# CDH-v3_7.net
KiCad netlist of a schematic drawn in EAGLE
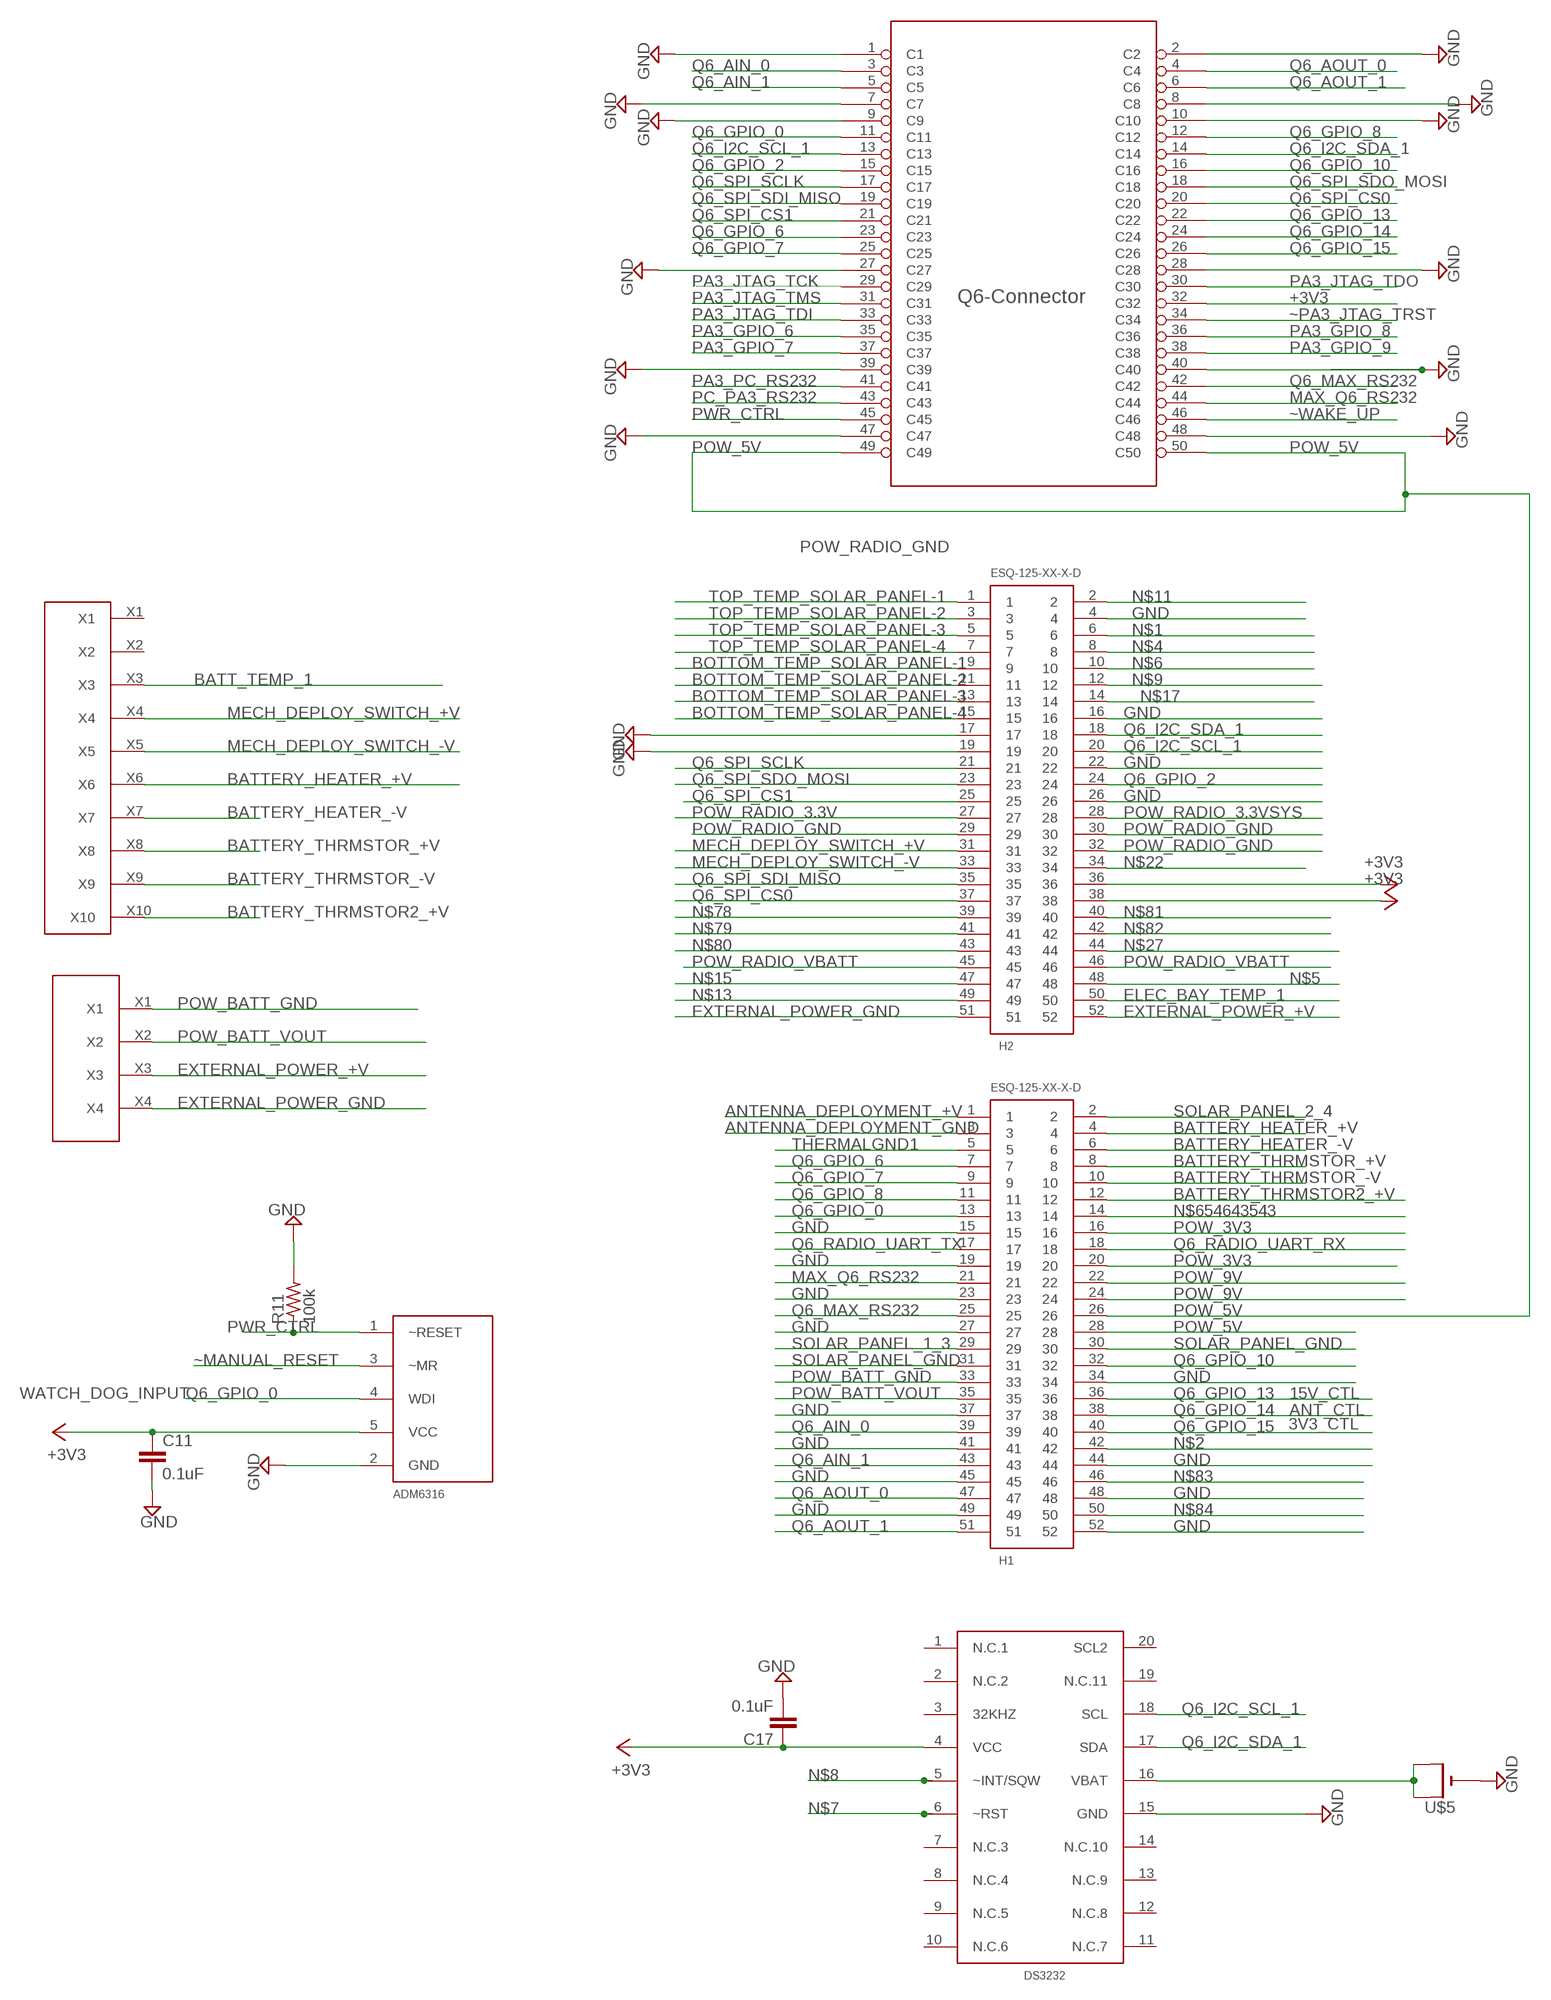
[diagram p0: schematic, sheet 1, part 1 of 2]
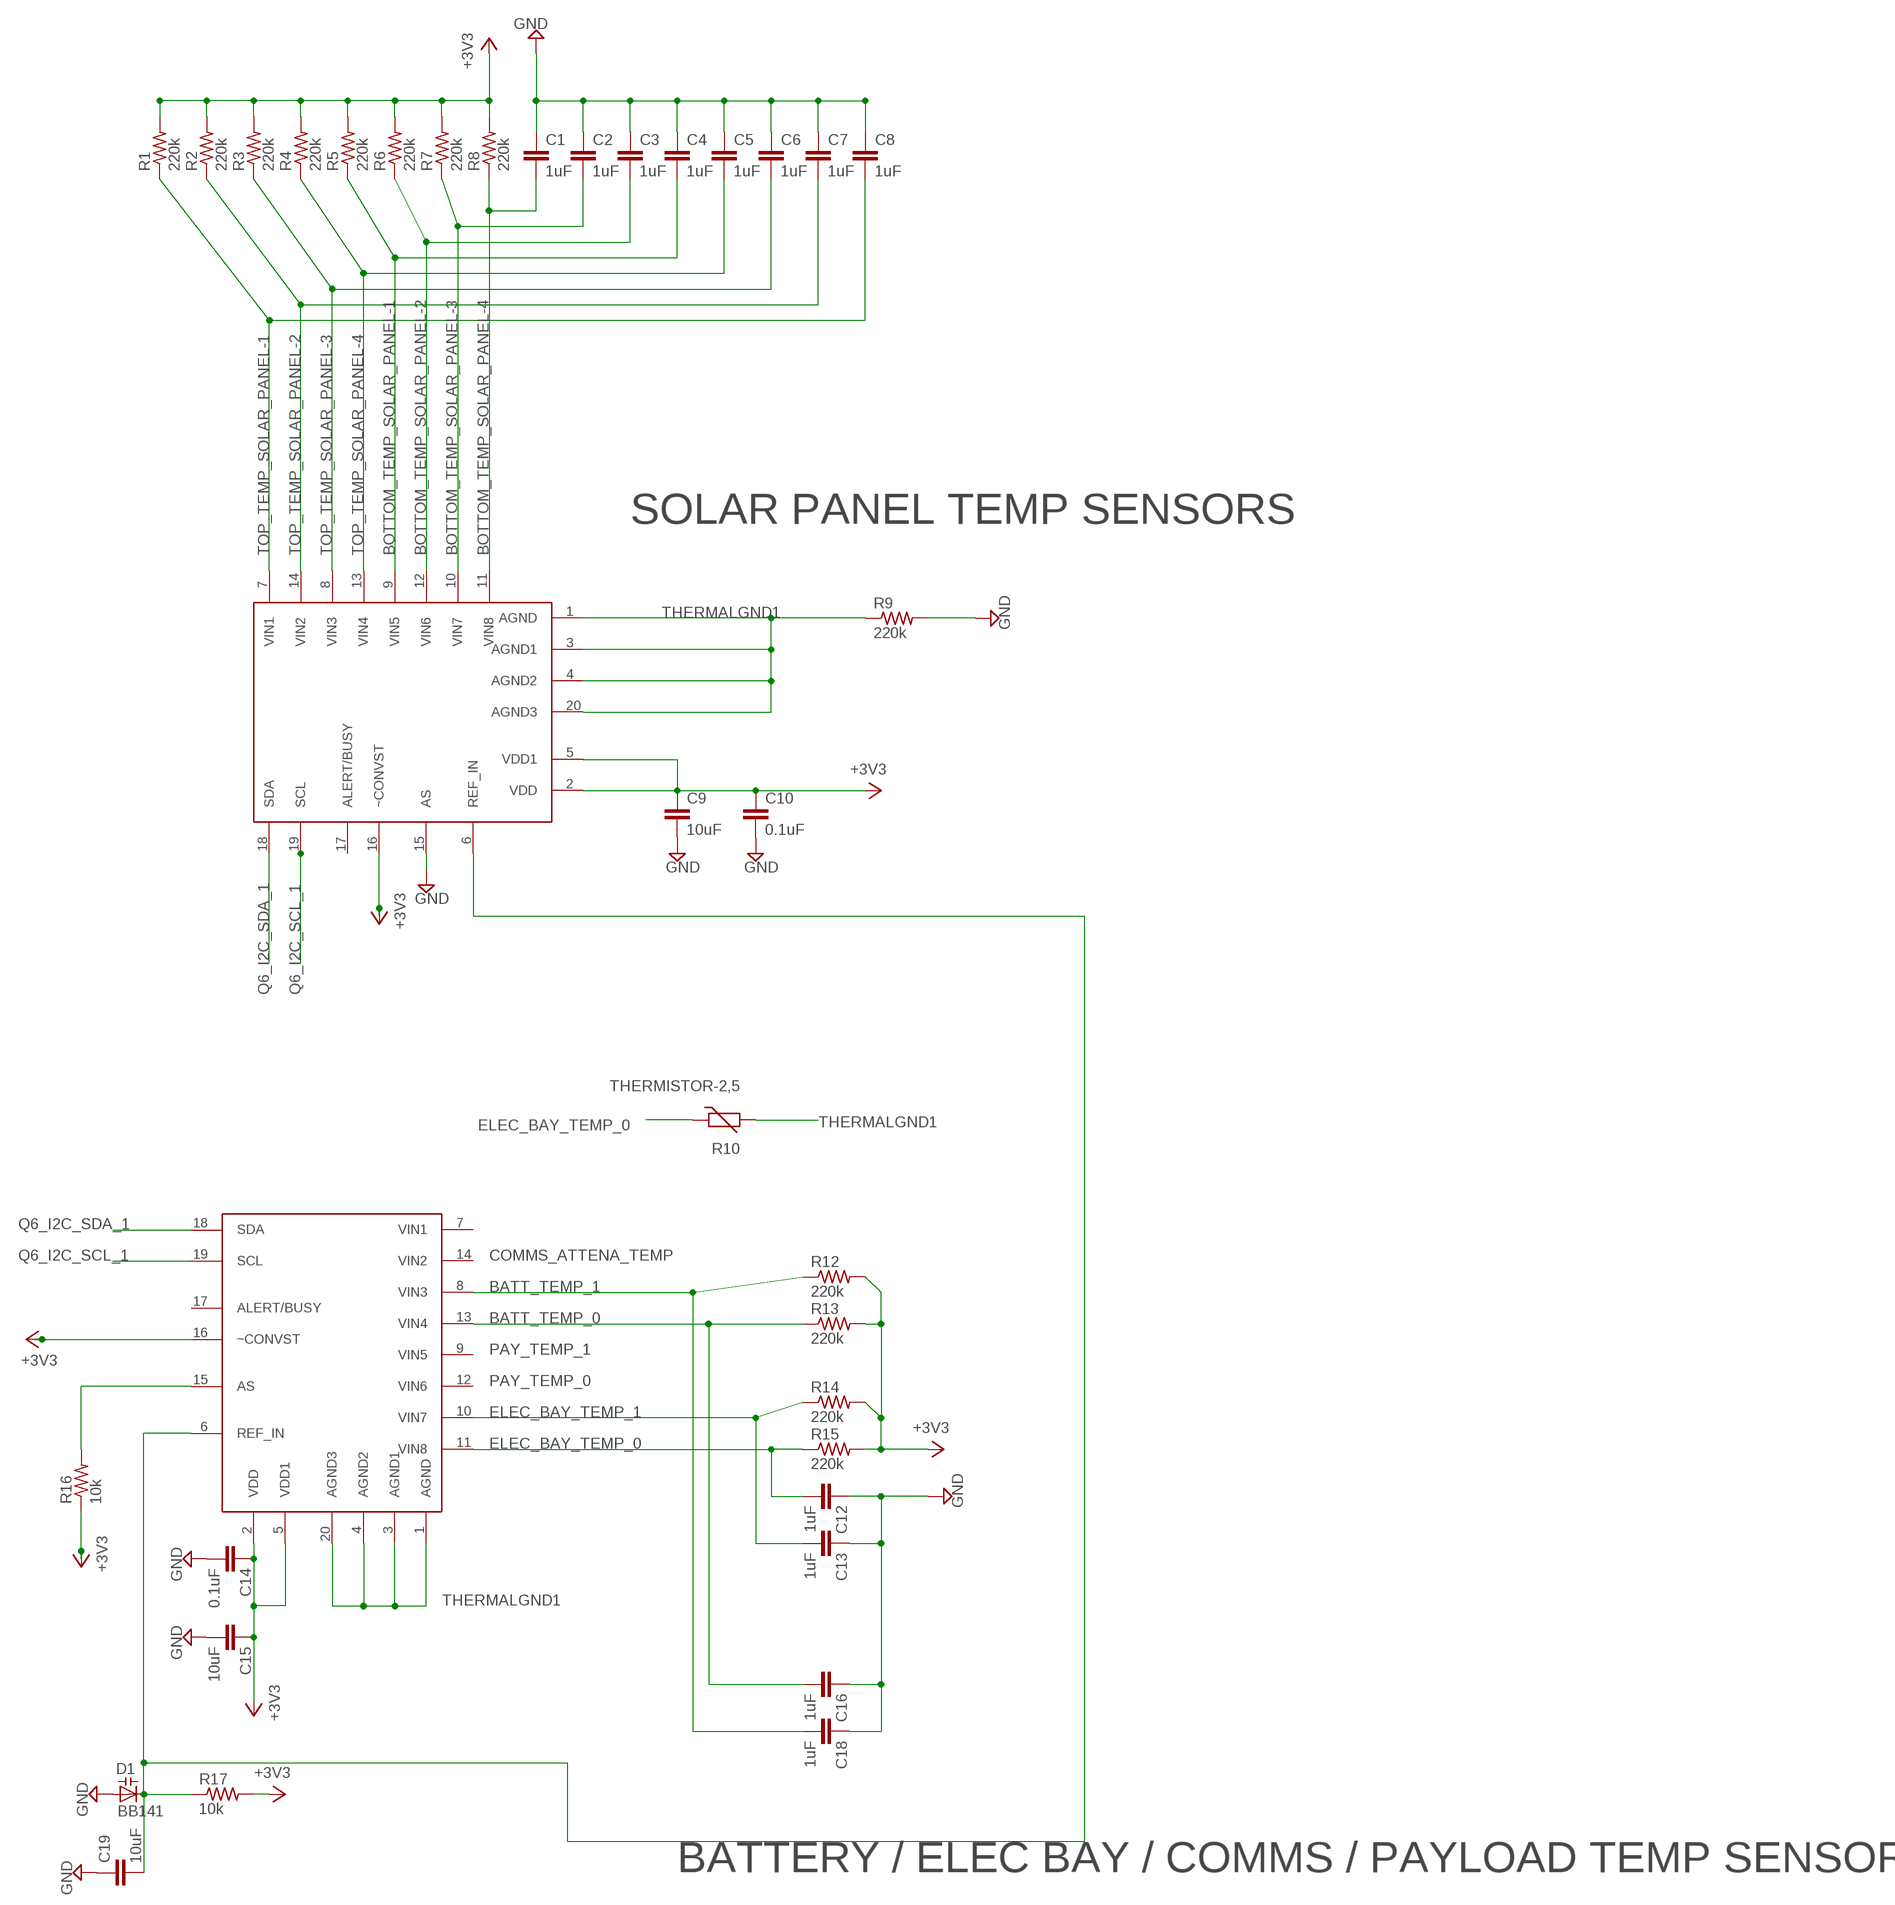
[diagram p1: schematic, sheet 1, part 2 of 2]

(export (version "E")
  (design (tool "Eeschema 10.0.6"))
  (components
    (comp (ref "ADC_TEMP_1")
      (value "AD7998-1")
      (footprint "eagle-import:TSSOP20")
      (libsource (lib "eagle-import") (part "AD7998-1"))
    )
    (comp (ref "ADC_TEMP_2")
      (value "AD7998-1")
      (footprint "eagle-import:TSSOP20")
      (libsource (lib "eagle-import") (part "AD7998-1"))
    )
    (comp (ref "C1")
      (value "1uF")
      (footprint "eagle-import:C2012")
      (libsource (lib "eagle-import") (part "C-EUC2012"))
    )
    (comp (ref "C2")
      (value "1uF")
      (footprint "eagle-import:C2012")
      (libsource (lib "eagle-import") (part "C-EUC2012"))
    )
    (comp (ref "C3")
      (value "1uF")
      (footprint "eagle-import:C2012")
      (libsource (lib "eagle-import") (part "C-EUC2012"))
    )
    (comp (ref "C4")
      (value "1uF")
      (footprint "eagle-import:C2012")
      (libsource (lib "eagle-import") (part "C-EUC2012"))
    )
    (comp (ref "C5")
      (value "1uF")
      (footprint "eagle-import:C2012")
      (libsource (lib "eagle-import") (part "C-EUC2012"))
    )
    (comp (ref "C6")
      (value "1uF")
      (footprint "eagle-import:C2012")
      (libsource (lib "eagle-import") (part "C-EUC2012"))
    )
    (comp (ref "C7")
      (value "1uF")
      (footprint "eagle-import:C2012")
      (libsource (lib "eagle-import") (part "C-EUC2012"))
    )
    (comp (ref "C8")
      (value "1uF")
      (footprint "eagle-import:C2012")
      (libsource (lib "eagle-import") (part "C-EUC2012"))
    )
    (comp (ref "C9")
      (value "10uF")
      (footprint "eagle-import:C2012")
      (libsource (lib "eagle-import") (part "C-EUC2012"))
    )
    (comp (ref "C10")
      (value "0.1uF")
      (footprint "eagle-import:C2012")
      (libsource (lib "eagle-import") (part "C-EUC2012"))
    )
    (comp (ref "C11")
      (value "0.1uF")
      (footprint "eagle-import:C2012")
      (libsource (lib "eagle-import") (part "C-EUC2012"))
    )
    (comp (ref "C12")
      (value "1uF")
      (footprint "eagle-import:C2012")
      (libsource (lib "eagle-import") (part "C-EUC2012"))
    )
    (comp (ref "C13")
      (value "1uF")
      (footprint "eagle-import:C2012")
      (libsource (lib "eagle-import") (part "C-EUC2012"))
    )
    (comp (ref "C14")
      (value "0.1uF")
      (footprint "eagle-import:C2012")
      (libsource (lib "eagle-import") (part "C-EUC2012"))
    )
    (comp (ref "C15")
      (value "10uF")
      (footprint "eagle-import:C2012")
      (libsource (lib "eagle-import") (part "C-EUC2012"))
    )
    (comp (ref "C16")
      (value "1uF")
      (footprint "eagle-import:C2012")
      (libsource (lib "eagle-import") (part "C-EUC2012"))
    )
    (comp (ref "C17")
      (value "0.1uF")
      (footprint "eagle-import:C2012")
      (libsource (lib "eagle-import") (part "C-EUC2012"))
    )
    (comp (ref "C18")
      (value "1uF")
      (footprint "eagle-import:C2012")
      (libsource (lib "eagle-import") (part "C-EUC2012"))
    )
    (comp (ref "C19")
      (value "10uF")
      (footprint "eagle-import:C2012")
      (libsource (lib "eagle-import") (part "C-EUC2012"))
    )
    (comp (ref "D1")
      (value "BB141")
      (footprint "eagle-import:SOD523")
      (libsource (lib "eagle-import") (part "BB141"))
    )
    (comp (ref "H1")
      (value "ESQ-125-XX-X-D")
      (footprint "eagle-import:ESQ-125-XX-X-D")
      (libsource (lib "eagle-import") (part "ESQ-125-XX-X-D"))
    )
    (comp (ref "H2")
      (value "ESQ-125-XX-X-D")
      (footprint "eagle-import:ESQ-125-XX-X-D")
      (libsource (lib "eagle-import") (part "ESQ-125-XX-X-D"))
    )
    (comp (ref "J2")
      (value "M80-5000000M1-10-331-000")
      (footprint "eagle-import:M80-5000000M1")
      (libsource (lib "eagle-import") (part "M80-5000000M1-10-331-000"))
    )
    (comp (ref "J3")
      (value "M80-5000000M1-10-331-00-000")
      (footprint "eagle-import:M80-5000000M1-04-331-00-000")
      (libsource (lib "eagle-import") (part "M80-5000000M1-10-331-00-000"))
    )
    (comp (ref "J4")
      (value "SMFC")
      (footprint "eagle-import:SFMC-107-01-XX-D")
      (libsource (lib "eagle-import") (part "SMFC"))
    )
    (comp (ref "R1")
      (value "220k")
      (footprint "eagle-import:R2012")
      (libsource (lib "eagle-import") (part "R-US_R2012"))
    )
    (comp (ref "R2")
      (value "220k")
      (footprint "eagle-import:R2012")
      (libsource (lib "eagle-import") (part "R-US_R2012"))
    )
    (comp (ref "R3")
      (value "220k")
      (footprint "eagle-import:R2012")
      (libsource (lib "eagle-import") (part "R-US_R2012"))
    )
    (comp (ref "R4")
      (value "220k")
      (footprint "eagle-import:R2012")
      (libsource (lib "eagle-import") (part "R-US_R2012"))
    )
    (comp (ref "R5")
      (value "220k")
      (footprint "eagle-import:R2012")
      (libsource (lib "eagle-import") (part "R-US_R2012"))
    )
    (comp (ref "R6")
      (value "220k")
      (footprint "eagle-import:R2012")
      (libsource (lib "eagle-import") (part "R-US_R2012"))
    )
    (comp (ref "R7")
      (value "220k")
      (footprint "eagle-import:R2012")
      (libsource (lib "eagle-import") (part "R-US_R2012"))
    )
    (comp (ref "R8")
      (value "220k")
      (footprint "eagle-import:R2012")
      (libsource (lib "eagle-import") (part "R-US_R2012"))
    )
    (comp (ref "R9")
      (value "220k")
      (footprint "eagle-import:R2012")
      (libsource (lib "eagle-import") (part "R-US_R2012"))
    )
    (comp (ref "R10")
      (value "THERMISTOR-2,5")
      (footprint "eagle-import:RS-2,5")
      (libsource (lib "eagle-import") (part "THERMISTOR-2,5"))
    )
    (comp (ref "R11")
      (value "100k")
      (footprint "eagle-import:R2012")
      (libsource (lib "eagle-import") (part "R-US_R2012"))
    )
    (comp (ref "R12")
      (value "220k")
      (footprint "eagle-import:R2012")
      (libsource (lib "eagle-import") (part "R-US_R2012"))
    )
    (comp (ref "R13")
      (value "220k")
      (footprint "eagle-import:R2012")
      (libsource (lib "eagle-import") (part "R-US_R2012"))
    )
    (comp (ref "R14")
      (value "220k")
      (footprint "eagle-import:R2012")
      (libsource (lib "eagle-import") (part "R-US_R2012"))
    )
    (comp (ref "R15")
      (value "220k")
      (footprint "eagle-import:R2012")
      (libsource (lib "eagle-import") (part "R-US_R2012"))
    )
    (comp (ref "R16")
      (value "10k")
      (footprint "eagle-import:R2012")
      (libsource (lib "eagle-import") (part "R-US_R2012"))
    )
    (comp (ref "R17")
      (value "10k")
      (footprint "eagle-import:R2012")
      (libsource (lib "eagle-import") (part "R-US_R2012"))
    )
    (comp (ref "U$4")
      (value "ADM6316/ADM6320")
      (footprint "eagle-import:SOT23-5")
      (libsource (lib "eagle-import") (part "ADM6316/ADM6320"))
    )
    (comp (ref "U$5")
      (value "CR1220SMT")
      (footprint "eagle-import:CR1220-SMD")
      (libsource (lib "eagle-import") (part "CR1220SMT"))
    )
    (comp (ref "U$6")
      (value "DS3232")
      (footprint "eagle-import:SO20L")
      (libsource (lib "eagle-import") (part "DS3232"))
    )
  )
  (nets
    (net (code "1") (name "+3V3") (class "Default")
      (node (ref "ADC_TEMP_1") (pin "16") (pinfunction "~{CONVST}_16") (pintype "bidirectional"))
      (node (ref "ADC_TEMP_1") (pin "2") (pinfunction "VDD_2") (pintype "bidirectional"))
      (node (ref "ADC_TEMP_1") (pin "5") (pinfunction "VDD1_5") (pintype "bidirectional"))
      (node (ref "ADC_TEMP_2") (pin "16") (pinfunction "~{CONVST}_16") (pintype "bidirectional"))
      (node (ref "ADC_TEMP_2") (pin "2") (pinfunction "VDD_2") (pintype "bidirectional"))
      (node (ref "ADC_TEMP_2") (pin "5") (pinfunction "VDD1_5") (pintype "bidirectional"))
      (node (ref "C10") (pin "1") (pinfunction "1_1") (pintype "passive"))
      (node (ref "C11") (pin "1") (pinfunction "1_1") (pintype "passive"))
      (node (ref "C14") (pin "1") (pinfunction "1_1") (pintype "passive"))
      (node (ref "C15") (pin "1") (pinfunction "1_1") (pintype "passive"))
      (node (ref "C17") (pin "1") (pinfunction "1_1") (pintype "passive"))
      (node (ref "C9") (pin "1") (pinfunction "1_1") (pintype "passive"))
      (node (ref "H2") (pin "36") (pinfunction "36_36") (pintype "bidirectional"))
      (node (ref "H2") (pin "38") (pinfunction "38_38") (pintype "bidirectional"))
      (node (ref "J4") (pin "32") (pinfunction "C32_32") (pintype "bidirectional"))
      (node (ref "R1") (pin "2") (pinfunction "2_2") (pintype "passive"))
      (node (ref "R12") (pin "2") (pinfunction "2_2") (pintype "passive"))
      (node (ref "R13") (pin "2") (pinfunction "2_2") (pintype "passive"))
      (node (ref "R14") (pin "2") (pinfunction "2_2") (pintype "passive"))
      (node (ref "R15") (pin "2") (pinfunction "2_2") (pintype "passive"))
      (node (ref "R16") (pin "1") (pinfunction "1_1") (pintype "passive"))
      (node (ref "R17") (pin "2") (pinfunction "2_2") (pintype "passive"))
      (node (ref "R2") (pin "2") (pinfunction "2_2") (pintype "passive"))
      (node (ref "R3") (pin "2") (pinfunction "2_2") (pintype "passive"))
      (node (ref "R4") (pin "2") (pinfunction "2_2") (pintype "passive"))
      (node (ref "R5") (pin "2") (pinfunction "2_2") (pintype "passive"))
      (node (ref "R6") (pin "2") (pinfunction "2_2") (pintype "passive"))
      (node (ref "R7") (pin "2") (pinfunction "2_2") (pintype "passive"))
      (node (ref "R8") (pin "2") (pinfunction "2_2") (pintype "passive"))
      (node (ref "U$4") (pin "5") (pinfunction "VCC_5") (pintype "bidirectional"))
      (node (ref "U$6") (pin "4") (pinfunction "VCC_4") (pintype "bidirectional"))
    )
    (net (code "2") (name "/ANTENNA_DEPLOYMENT_+V") (class "Default")
      (node (ref "H1") (pin "1") (pinfunction "1_1") (pintype "bidirectional"))
    )
    (net (code "3") (name "/ANTENNA_DEPLOYMENT_GND") (class "Default")
      (node (ref "H1") (pin "3") (pinfunction "3_3") (pintype "bidirectional"))
    )
    (net (code "4") (name "/BATTERY_HEATER_+V") (class "Default")
      (node (ref "H1") (pin "4") (pinfunction "4_4") (pintype "bidirectional"))
      (node (ref "J2") (pin "X6") (pinfunction "X6_X6") (pintype "bidirectional"))
    )
    (net (code "5") (name "/BATTERY_HEATER_-V") (class "Default")
      (node (ref "H1") (pin "6") (pinfunction "6_6") (pintype "bidirectional"))
      (node (ref "J2") (pin "X7") (pinfunction "X7_X7") (pintype "bidirectional"))
    )
    (net (code "6") (name "/BATTERY_THRMSTOR2_+V") (class "Default")
      (node (ref "H1") (pin "12") (pinfunction "12_12") (pintype "bidirectional"))
      (node (ref "J2") (pin "X10") (pinfunction "X10_X10") (pintype "bidirectional"))
    )
    (net (code "7") (name "/BATTERY_THRMSTOR_+V") (class "Default")
      (node (ref "H1") (pin "8") (pinfunction "8_8") (pintype "bidirectional"))
      (node (ref "J2") (pin "X8") (pinfunction "X8_X8") (pintype "bidirectional"))
    )
    (net (code "8") (name "/BATTERY_THRMSTOR_-V") (class "Default")
      (node (ref "H1") (pin "10") (pinfunction "10_10") (pintype "bidirectional"))
      (node (ref "J2") (pin "X9") (pinfunction "X9_X9") (pintype "bidirectional"))
    )
    (net (code "9") (name "/BATT_TEMP_1") (class "Default")
      (node (ref "ADC_TEMP_2") (pin "8") (pinfunction "VIN3_8") (pintype "bidirectional"))
      (node (ref "C18") (pin "2") (pinfunction "2_2") (pintype "passive"))
      (node (ref "J2") (pin "X3") (pinfunction "X3_X3") (pintype "bidirectional"))
      (node (ref "R12") (pin "1") (pinfunction "1_1") (pintype "passive"))
    )
    (net (code "10") (name "/BOTTOM_TEMP_SOLAR_PANEL-1") (class "Default")
      (node (ref "ADC_TEMP_1") (pin "9") (pinfunction "VIN5_9") (pintype "bidirectional"))
      (node (ref "C4") (pin "2") (pinfunction "2_2") (pintype "passive"))
      (node (ref "H2") (pin "9") (pinfunction "9_9") (pintype "bidirectional"))
      (node (ref "R5") (pin "1") (pinfunction "1_1") (pintype "passive"))
    )
    (net (code "11") (name "/BOTTOM_TEMP_SOLAR_PANEL-2") (class "Default")
      (node (ref "ADC_TEMP_1") (pin "12") (pinfunction "VIN6_12") (pintype "bidirectional"))
      (node (ref "C3") (pin "2") (pinfunction "2_2") (pintype "passive"))
      (node (ref "H2") (pin "11") (pinfunction "11_11") (pintype "bidirectional"))
      (node (ref "R6") (pin "1") (pinfunction "1_1") (pintype "passive"))
    )
    (net (code "12") (name "/BOTTOM_TEMP_SOLAR_PANEL-3") (class "Default")
      (node (ref "ADC_TEMP_1") (pin "10") (pinfunction "VIN7_10") (pintype "bidirectional"))
      (node (ref "C2") (pin "2") (pinfunction "2_2") (pintype "passive"))
      (node (ref "H2") (pin "13") (pinfunction "13_13") (pintype "bidirectional"))
      (node (ref "R7") (pin "1") (pinfunction "1_1") (pintype "passive"))
    )
    (net (code "13") (name "/BOTTOM_TEMP_SOLAR_PANEL-4") (class "Default")
      (node (ref "ADC_TEMP_1") (pin "11") (pinfunction "VIN8_11") (pintype "bidirectional"))
      (node (ref "C1") (pin "2") (pinfunction "2_2") (pintype "passive"))
      (node (ref "H2") (pin "15") (pinfunction "15_15") (pintype "bidirectional"))
      (node (ref "R8") (pin "1") (pinfunction "1_1") (pintype "passive"))
    )
    (net (code "14") (name "/ELEC_BAY_TEMP_0") (class "Default")
      (node (ref "ADC_TEMP_2") (pin "11") (pinfunction "VIN8_11") (pintype "bidirectional"))
      (node (ref "C12") (pin "2") (pinfunction "2_2") (pintype "passive"))
      (node (ref "R10") (pin "1") (pinfunction "1_1") (pintype "passive"))
      (node (ref "R15") (pin "1") (pinfunction "1_1") (pintype "passive"))
    )
    (net (code "15") (name "/ELEC_BAY_TEMP_1") (class "Default")
      (node (ref "ADC_TEMP_2") (pin "10") (pinfunction "VIN7_10") (pintype "bidirectional"))
      (node (ref "C13") (pin "2") (pinfunction "2_2") (pintype "passive"))
      (node (ref "H2") (pin "50") (pinfunction "50_50") (pintype "bidirectional"))
      (node (ref "R14") (pin "1") (pinfunction "1_1") (pintype "passive"))
    )
    (net (code "16") (name "/EXTERNAL_POWER_+V") (class "Default")
      (node (ref "H2") (pin "52") (pinfunction "52_52") (pintype "bidirectional"))
      (node (ref "J3") (pin "X3") (pinfunction "X3_X3") (pintype "bidirectional"))
    )
    (net (code "17") (name "/EXTERNAL_POWER_GND") (class "Default")
      (node (ref "H2") (pin "51") (pinfunction "51_51") (pintype "bidirectional"))
      (node (ref "J3") (pin "X4") (pinfunction "X4_X4") (pintype "bidirectional"))
    )
    (net (code "18") (name "/MAX_Q6_RS232") (class "Default")
      (node (ref "H1") (pin "21") (pinfunction "21_21") (pintype "bidirectional"))
      (node (ref "J4") (pin "44") (pinfunction "C44_44") (pintype "bidirectional"))
    )
    (net (code "19") (name "/MECH_DEPLOY_SWITCH_+V") (class "Default")
      (node (ref "H2") (pin "31") (pinfunction "31_31") (pintype "bidirectional"))
      (node (ref "J2") (pin "X4") (pinfunction "X4_X4") (pintype "bidirectional"))
    )
    (net (code "20") (name "/MECH_DEPLOY_SWITCH_-V") (class "Default")
      (node (ref "H2") (pin "33") (pinfunction "33_33") (pintype "bidirectional"))
      (node (ref "J2") (pin "X5") (pinfunction "X5_X5") (pintype "bidirectional"))
    )
    (net (code "21") (name "/N$1") (class "Default")
      (node (ref "H2") (pin "6") (pinfunction "6_6") (pintype "bidirectional"))
    )
    (net (code "22") (name "/N$2") (class "Default")
      (node (ref "H1") (pin "42") (pinfunction "42_42") (pintype "bidirectional"))
    )
    (net (code "23") (name "/N$4") (class "Default")
      (node (ref "H2") (pin "8") (pinfunction "8_8") (pintype "bidirectional"))
    )
    (net (code "24") (name "/N$5") (class "Default")
      (node (ref "H2") (pin "48") (pinfunction "48_48") (pintype "bidirectional"))
    )
    (net (code "25") (name "/N$6") (class "Default")
      (node (ref "H2") (pin "10") (pinfunction "10_10") (pintype "bidirectional"))
    )
    (net (code "26") (name "/N$7") (class "Default")
      (node (ref "U$6") (pin "6") (pinfunction "~{RST}_6") (pintype "bidirectional"))
    )
    (net (code "27") (name "/N$8") (class "Default")
      (node (ref "U$6") (pin "5") (pinfunction "~{INT/SQW}_5") (pintype "bidirectional"))
    )
    (net (code "28") (name "/N$9") (class "Default")
      (node (ref "H2") (pin "12") (pinfunction "12_12") (pintype "bidirectional"))
    )
    (net (code "29") (name "/N$11") (class "Default")
      (node (ref "H2") (pin "2") (pinfunction "2_2") (pintype "bidirectional"))
    )
    (net (code "30") (name "/N$13") (class "Default")
      (node (ref "H2") (pin "49") (pinfunction "49_49") (pintype "bidirectional"))
    )
    (net (code "31") (name "/N$15") (class "Default")
      (node (ref "H2") (pin "47") (pinfunction "47_47") (pintype "bidirectional"))
    )
    (net (code "32") (name "/N$17") (class "Default")
      (node (ref "H2") (pin "14") (pinfunction "14_14") (pintype "bidirectional"))
    )
    (net (code "33") (name "/N$22") (class "Default")
      (node (ref "H2") (pin "34") (pinfunction "34_34") (pintype "bidirectional"))
    )
    (net (code "34") (name "/N$27") (class "Default")
      (node (ref "H2") (pin "44") (pinfunction "44_44") (pintype "bidirectional"))
    )
    (net (code "35") (name "/N$78") (class "Default")
      (node (ref "H2") (pin "39") (pinfunction "39_39") (pintype "bidirectional"))
    )
    (net (code "36") (name "/N$79") (class "Default")
      (node (ref "H2") (pin "41") (pinfunction "41_41") (pintype "bidirectional"))
    )
    (net (code "37") (name "/N$80") (class "Default")
      (node (ref "H2") (pin "43") (pinfunction "43_43") (pintype "bidirectional"))
    )
    (net (code "38") (name "/N$81") (class "Default")
      (node (ref "H2") (pin "40") (pinfunction "40_40") (pintype "bidirectional"))
    )
    (net (code "39") (name "/N$82") (class "Default")
      (node (ref "H2") (pin "42") (pinfunction "42_42") (pintype "bidirectional"))
    )
    (net (code "40") (name "/N$83") (class "Default")
      (node (ref "H1") (pin "46") (pinfunction "46_46") (pintype "bidirectional"))
    )
    (net (code "41") (name "/N$84") (class "Default")
      (node (ref "H1") (pin "50") (pinfunction "50_50") (pintype "bidirectional"))
    )
    (net (code "42") (name "/N$654643543") (class "Default")
      (node (ref "H1") (pin "14") (pinfunction "14_14") (pintype "bidirectional"))
    )
    (net (code "43") (name "/PA3_GPIO_6") (class "Default")
      (node (ref "J4") (pin "35") (pinfunction "C35_35") (pintype "bidirectional"))
    )
    (net (code "44") (name "/PA3_GPIO_7") (class "Default")
      (node (ref "J4") (pin "37") (pinfunction "C37_37") (pintype "bidirectional"))
    )
    (net (code "45") (name "/PA3_GPIO_8") (class "Default")
      (node (ref "J4") (pin "36") (pinfunction "C36_36") (pintype "bidirectional"))
    )
    (net (code "46") (name "/PA3_GPIO_9") (class "Default")
      (node (ref "J4") (pin "38") (pinfunction "C38_38") (pintype "bidirectional"))
    )
    (net (code "47") (name "/PA3_JTAG_TCK") (class "Default")
      (node (ref "J4") (pin "29") (pinfunction "C29_29") (pintype "bidirectional"))
    )
    (net (code "48") (name "/PA3_JTAG_TDI") (class "Default")
      (node (ref "J4") (pin "33") (pinfunction "C33_33") (pintype "bidirectional"))
    )
    (net (code "49") (name "/PA3_JTAG_TDO") (class "Default")
      (node (ref "J4") (pin "30") (pinfunction "C30_30") (pintype "bidirectional"))
    )
    (net (code "50") (name "/PA3_JTAG_TMS") (class "Default")
      (node (ref "J4") (pin "31") (pinfunction "C31_31") (pintype "bidirectional"))
    )
    (net (code "51") (name "/PA3_PC_RS232") (class "Default")
      (node (ref "J4") (pin "41") (pinfunction "C41_41") (pintype "bidirectional"))
    )
    (net (code "52") (name "/PC_PA3_RS232") (class "Default")
      (node (ref "J4") (pin "43") (pinfunction "C43_43") (pintype "bidirectional"))
    )
    (net (code "53") (name "/POW_3V3") (class "Default")
      (node (ref "H1") (pin "16") (pinfunction "16_16") (pintype "bidirectional"))
      (node (ref "H1") (pin "20") (pinfunction "20_20") (pintype "bidirectional"))
    )
    (net (code "54") (name "/POW_5V") (class "Default")
      (node (ref "H1") (pin "26") (pinfunction "26_26") (pintype "bidirectional"))
      (node (ref "H1") (pin "28") (pinfunction "28_28") (pintype "bidirectional"))
      (node (ref "J4") (pin "49") (pinfunction "C49_49") (pintype "bidirectional"))
      (node (ref "J4") (pin "50") (pinfunction "C50_50") (pintype "bidirectional"))
    )
    (net (code "55") (name "/POW_9V") (class "Default")
      (node (ref "H1") (pin "22") (pinfunction "22_22") (pintype "bidirectional"))
      (node (ref "H1") (pin "24") (pinfunction "24_24") (pintype "bidirectional"))
    )
    (net (code "56") (name "/POW_BATT_GND") (class "Default")
      (node (ref "H1") (pin "33") (pinfunction "33_33") (pintype "bidirectional"))
      (node (ref "J3") (pin "X1") (pinfunction "X1_X1") (pintype "bidirectional"))
    )
    (net (code "57") (name "/POW_BATT_VOUT") (class "Default")
      (node (ref "H1") (pin "35") (pinfunction "35_35") (pintype "bidirectional"))
      (node (ref "J3") (pin "X2") (pinfunction "X2_X2") (pintype "bidirectional"))
    )
    (net (code "58") (name "/POW_RADIO_3.3V") (class "Default")
      (node (ref "H2") (pin "27") (pinfunction "27_27") (pintype "bidirectional"))
    )
    (net (code "59") (name "/POW_RADIO_3.3VSYS") (class "Default")
      (node (ref "H2") (pin "28") (pinfunction "28_28") (pintype "bidirectional"))
    )
    (net (code "60") (name "/POW_RADIO_GND") (class "Default")
      (node (ref "H2") (pin "29") (pinfunction "29_29") (pintype "bidirectional"))
      (node (ref "H2") (pin "30") (pinfunction "30_30") (pintype "bidirectional"))
      (node (ref "H2") (pin "32") (pinfunction "32_32") (pintype "bidirectional"))
    )
    (net (code "61") (name "/POW_RADIO_VBATT") (class "Default")
      (node (ref "H2") (pin "45") (pinfunction "45_45") (pintype "bidirectional"))
      (node (ref "H2") (pin "46") (pinfunction "46_46") (pintype "bidirectional"))
    )
    (net (code "62") (name "/PWR_CTRL") (class "Default")
      (node (ref "J4") (pin "45") (pinfunction "C45_45") (pintype "bidirectional"))
      (node (ref "R11") (pin "1") (pinfunction "1_1") (pintype "passive"))
      (node (ref "U$4") (pin "1") (pinfunction "~{RESET}_1") (pintype "bidirectional"))
    )
    (net (code "63") (name "/Q6_AIN_0") (class "Default")
      (node (ref "H1") (pin "39") (pinfunction "39_39") (pintype "bidirectional"))
      (node (ref "J4") (pin "3") (pinfunction "C3_3") (pintype "bidirectional"))
    )
    (net (code "64") (name "/Q6_AIN_1") (class "Default")
      (node (ref "H1") (pin "43") (pinfunction "43_43") (pintype "bidirectional"))
      (node (ref "J4") (pin "5") (pinfunction "C5_5") (pintype "bidirectional"))
    )
    (net (code "65") (name "/Q6_AOUT_0") (class "Default")
      (node (ref "H1") (pin "47") (pinfunction "47_47") (pintype "bidirectional"))
      (node (ref "J4") (pin "4") (pinfunction "C4_4") (pintype "bidirectional"))
    )
    (net (code "66") (name "/Q6_AOUT_1") (class "Default")
      (node (ref "H1") (pin "51") (pinfunction "51_51") (pintype "bidirectional"))
      (node (ref "J4") (pin "6") (pinfunction "C6_6") (pintype "bidirectional"))
    )
    (net (code "67") (name "/Q6_GPIO_0") (class "Default")
      (node (ref "H1") (pin "13") (pinfunction "13_13") (pintype "bidirectional"))
      (node (ref "J4") (pin "11") (pinfunction "C11_11") (pintype "bidirectional"))
      (node (ref "U$4") (pin "4") (pinfunction "WDI_4") (pintype "bidirectional"))
    )
    (net (code "68") (name "/Q6_GPIO_2") (class "Default")
      (node (ref "H2") (pin "24") (pinfunction "24_24") (pintype "bidirectional"))
      (node (ref "J4") (pin "15") (pinfunction "C15_15") (pintype "bidirectional"))
    )
    (net (code "69") (name "/Q6_GPIO_6") (class "Default")
      (node (ref "H1") (pin "7") (pinfunction "7_7") (pintype "bidirectional"))
      (node (ref "J4") (pin "23") (pinfunction "C23_23") (pintype "bidirectional"))
    )
    (net (code "70") (name "/Q6_GPIO_7") (class "Default")
      (node (ref "H1") (pin "9") (pinfunction "9_9") (pintype "bidirectional"))
      (node (ref "J4") (pin "25") (pinfunction "C25_25") (pintype "bidirectional"))
    )
    (net (code "71") (name "/Q6_GPIO_8") (class "Default")
      (node (ref "H1") (pin "11") (pinfunction "11_11") (pintype "bidirectional"))
      (node (ref "J4") (pin "12") (pinfunction "C12_12") (pintype "bidirectional"))
    )
    (net (code "72") (name "/Q6_GPIO_10") (class "Default")
      (node (ref "H1") (pin "32") (pinfunction "32_32") (pintype "bidirectional"))
      (node (ref "J4") (pin "16") (pinfunction "C16_16") (pintype "bidirectional"))
    )
    (net (code "73") (name "/Q6_GPIO_13") (class "Default")
      (node (ref "H1") (pin "36") (pinfunction "36_36") (pintype "bidirectional"))
      (node (ref "J4") (pin "22") (pinfunction "C22_22") (pintype "bidirectional"))
    )
    (net (code "74") (name "/Q6_GPIO_14") (class "Default")
      (node (ref "H1") (pin "38") (pinfunction "38_38") (pintype "bidirectional"))
      (node (ref "J4") (pin "24") (pinfunction "C24_24") (pintype "bidirectional"))
    )
    (net (code "75") (name "/Q6_GPIO_15") (class "Default")
      (node (ref "H1") (pin "40") (pinfunction "40_40") (pintype "bidirectional"))
      (node (ref "J4") (pin "26") (pinfunction "C26_26") (pintype "bidirectional"))
    )
    (net (code "76") (name "/Q6_I2C_SCL_1") (class "Default")
      (node (ref "ADC_TEMP_1") (pin "19") (pinfunction "SCL_19") (pintype "bidirectional"))
      (node (ref "ADC_TEMP_2") (pin "19") (pinfunction "SCL_19") (pintype "bidirectional"))
      (node (ref "H2") (pin "20") (pinfunction "20_20") (pintype "bidirectional"))
      (node (ref "J4") (pin "13") (pinfunction "C13_13") (pintype "bidirectional"))
      (node (ref "U$6") (pin "18") (pinfunction "SCL_18") (pintype "bidirectional"))
    )
    (net (code "77") (name "/Q6_I2C_SDA_1") (class "Default")
      (node (ref "ADC_TEMP_1") (pin "18") (pinfunction "SDA_18") (pintype "bidirectional"))
      (node (ref "ADC_TEMP_2") (pin "18") (pinfunction "SDA_18") (pintype "bidirectional"))
      (node (ref "H2") (pin "18") (pinfunction "18_18") (pintype "bidirectional"))
      (node (ref "J4") (pin "14") (pinfunction "C14_14") (pintype "bidirectional"))
      (node (ref "U$6") (pin "17") (pinfunction "SDA_17") (pintype "bidirectional"))
    )
    (net (code "78") (name "/Q6_MAX_RS232") (class "Default")
      (node (ref "H1") (pin "25") (pinfunction "25_25") (pintype "bidirectional"))
      (node (ref "J4") (pin "42") (pinfunction "C42_42") (pintype "bidirectional"))
    )
    (net (code "79") (name "/Q6_RADIO_UART_RX") (class "Default")
      (node (ref "H1") (pin "18") (pinfunction "18_18") (pintype "bidirectional"))
    )
    (net (code "80") (name "/Q6_RADIO_UART_TX") (class "Default")
      (node (ref "H1") (pin "17") (pinfunction "17_17") (pintype "bidirectional"))
    )
    (net (code "81") (name "/Q6_SPI_CS0") (class "Default")
      (node (ref "H2") (pin "37") (pinfunction "37_37") (pintype "bidirectional"))
      (node (ref "J4") (pin "20") (pinfunction "C20_20") (pintype "bidirectional"))
    )
    (net (code "82") (name "/Q6_SPI_CS1") (class "Default")
      (node (ref "H2") (pin "25") (pinfunction "25_25") (pintype "bidirectional"))
      (node (ref "J4") (pin "21") (pinfunction "C21_21") (pintype "bidirectional"))
    )
    (net (code "83") (name "/Q6_SPI_SCLK") (class "Default")
      (node (ref "H2") (pin "21") (pinfunction "21_21") (pintype "bidirectional"))
      (node (ref "J4") (pin "17") (pinfunction "C17_17") (pintype "bidirectional"))
    )
    (net (code "84") (name "/Q6_SPI_SDI_MISO") (class "Default")
      (node (ref "H2") (pin "35") (pinfunction "35_35") (pintype "bidirectional"))
      (node (ref "J4") (pin "19") (pinfunction "C19_19") (pintype "bidirectional"))
    )
    (net (code "85") (name "/Q6_SPI_SDO_MOSI") (class "Default")
      (node (ref "H2") (pin "23") (pinfunction "23_23") (pintype "bidirectional"))
      (node (ref "J4") (pin "18") (pinfunction "C18_18") (pintype "bidirectional"))
    )
    (net (code "86") (name "/SOLAR_PANEL_1_3") (class "Default")
      (node (ref "H1") (pin "29") (pinfunction "29_29") (pintype "bidirectional"))
    )
    (net (code "87") (name "/SOLAR_PANEL_GND") (class "Default")
      (node (ref "H1") (pin "30") (pinfunction "30_30") (pintype "bidirectional"))
      (node (ref "H1") (pin "31") (pinfunction "31_31") (pintype "bidirectional"))
    )
    (net (code "88") (name "/THERMALGND1") (class "Default")
      (node (ref "ADC_TEMP_1") (pin "1") (pinfunction "AGND_1") (pintype "bidirectional"))
      (node (ref "ADC_TEMP_1") (pin "20") (pinfunction "AGND3_20") (pintype "bidirectional"))
      (node (ref "ADC_TEMP_1") (pin "3") (pinfunction "AGND1_3") (pintype "bidirectional"))
      (node (ref "ADC_TEMP_1") (pin "4") (pinfunction "AGND2_4") (pintype "bidirectional"))
      (node (ref "ADC_TEMP_2") (pin "1") (pinfunction "AGND_1") (pintype "bidirectional"))
      (node (ref "ADC_TEMP_2") (pin "20") (pinfunction "AGND3_20") (pintype "bidirectional"))
      (node (ref "ADC_TEMP_2") (pin "3") (pinfunction "AGND1_3") (pintype "bidirectional"))
      (node (ref "ADC_TEMP_2") (pin "4") (pinfunction "AGND2_4") (pintype "bidirectional"))
      (node (ref "H1") (pin "5") (pinfunction "5_5") (pintype "bidirectional"))
      (node (ref "R10") (pin "2") (pinfunction "2_2") (pintype "passive"))
      (node (ref "R9") (pin "1") (pinfunction "1_1") (pintype "passive"))
    )
    (net (code "89") (name "/TOP_TEMP_SOLAR_PANEL-1") (class "Default")
      (node (ref "ADC_TEMP_1") (pin "7") (pinfunction "VIN1_7") (pintype "bidirectional"))
      (node (ref "C8") (pin "2") (pinfunction "2_2") (pintype "passive"))
      (node (ref "H2") (pin "1") (pinfunction "1_1") (pintype "bidirectional"))
      (node (ref "R1") (pin "1") (pinfunction "1_1") (pintype "passive"))
    )
    (net (code "90") (name "/TOP_TEMP_SOLAR_PANEL-2") (class "Default")
      (node (ref "ADC_TEMP_1") (pin "14") (pinfunction "VIN2_14") (pintype "bidirectional"))
      (node (ref "C7") (pin "2") (pinfunction "2_2") (pintype "passive"))
      (node (ref "H2") (pin "3") (pinfunction "3_3") (pintype "bidirectional"))
      (node (ref "R2") (pin "1") (pinfunction "1_1") (pintype "passive"))
    )
    (net (code "91") (name "/TOP_TEMP_SOLAR_PANEL-3") (class "Default")
      (node (ref "ADC_TEMP_1") (pin "8") (pinfunction "VIN3_8") (pintype "bidirectional"))
      (node (ref "C6") (pin "2") (pinfunction "2_2") (pintype "passive"))
      (node (ref "H2") (pin "5") (pinfunction "5_5") (pintype "bidirectional"))
      (node (ref "R3") (pin "1") (pinfunction "1_1") (pintype "passive"))
    )
    (net (code "92") (name "/TOP_TEMP_SOLAR_PANEL-4") (class "Default")
      (node (ref "ADC_TEMP_1") (pin "13") (pinfunction "VIN4_13") (pintype "bidirectional"))
      (node (ref "C5") (pin "2") (pinfunction "2_2") (pintype "passive"))
      (node (ref "H2") (pin "7") (pinfunction "7_7") (pintype "bidirectional"))
      (node (ref "R4") (pin "1") (pinfunction "1_1") (pintype "passive"))
    )
    (net (code "93") (name "/~{MANUAL_RESET}") (class "Default")
      (node (ref "U$4") (pin "3") (pinfunction "~{MR}_3") (pintype "bidirectional"))
    )
    (net (code "94") (name "/~{PA3_JTAG_TRST}") (class "Default")
      (node (ref "J4") (pin "34") (pinfunction "C34_34") (pintype "bidirectional"))
    )
    (net (code "95") (name "/~{WAKE_UP}") (class "Default")
      (node (ref "J4") (pin "46") (pinfunction "C46_46") (pintype "bidirectional"))
    )
    (net (code "96") (name "GND") (class "Default")
      (node (ref "ADC_TEMP_1") (pin "15") (pinfunction "AS_15") (pintype "bidirectional"))
      (node (ref "C1") (pin "1") (pinfunction "1_1") (pintype "passive"))
      (node (ref "C10") (pin "2") (pinfunction "2_2") (pintype "passive"))
      (node (ref "C11") (pin "2") (pinfunction "2_2") (pintype "passive"))
      (node (ref "C12") (pin "1") (pinfunction "1_1") (pintype "passive"))
      (node (ref "C13") (pin "1") (pinfunction "1_1") (pintype "passive"))
      (node (ref "C14") (pin "2") (pinfunction "2_2") (pintype "passive"))
      (node (ref "C15") (pin "2") (pinfunction "2_2") (pintype "passive"))
      (node (ref "C16") (pin "1") (pinfunction "1_1") (pintype "passive"))
      (node (ref "C17") (pin "2") (pinfunction "2_2") (pintype "passive"))
      (node (ref "C18") (pin "1") (pinfunction "1_1") (pintype "passive"))
      (node (ref "C19") (pin "1") (pinfunction "1_1") (pintype "passive"))
      (node (ref "C2") (pin "1") (pinfunction "1_1") (pintype "passive"))
      (node (ref "C3") (pin "1") (pinfunction "1_1") (pintype "passive"))
      (node (ref "C4") (pin "1") (pinfunction "1_1") (pintype "passive"))
      (node (ref "C5") (pin "1") (pinfunction "1_1") (pintype "passive"))
      (node (ref "C6") (pin "1") (pinfunction "1_1") (pintype "passive"))
      (node (ref "C7") (pin "1") (pinfunction "1_1") (pintype "passive"))
      (node (ref "C8") (pin "1") (pinfunction "1_1") (pintype "passive"))
      (node (ref "C9") (pin "2") (pinfunction "2_2") (pintype "passive"))
      (node (ref "D1") (pin "A") (pinfunction "A_A") (pintype "passive"))
      (node (ref "H1") (pin "15") (pinfunction "15_15") (pintype "bidirectional"))
      (node (ref "H1") (pin "19") (pinfunction "19_19") (pintype "bidirectional"))
      (node (ref "H1") (pin "23") (pinfunction "23_23") (pintype "bidirectional"))
      (node (ref "H1") (pin "27") (pinfunction "27_27") (pintype "bidirectional"))
      (node (ref "H1") (pin "34") (pinfunction "34_34") (pintype "bidirectional"))
      (node (ref "H1") (pin "37") (pinfunction "37_37") (pintype "bidirectional"))
      (node (ref "H1") (pin "41") (pinfunction "41_41") (pintype "bidirectional"))
      (node (ref "H1") (pin "44") (pinfunction "44_44") (pintype "bidirectional"))
      (node (ref "H1") (pin "45") (pinfunction "45_45") (pintype "bidirectional"))
      (node (ref "H1") (pin "48") (pinfunction "48_48") (pintype "bidirectional"))
      (node (ref "H1") (pin "49") (pinfunction "49_49") (pintype "bidirectional"))
      (node (ref "H1") (pin "52") (pinfunction "52_52") (pintype "bidirectional"))
      (node (ref "H2") (pin "16") (pinfunction "16_16") (pintype "bidirectional"))
      (node (ref "H2") (pin "17") (pinfunction "17_17") (pintype "bidirectional"))
      (node (ref "H2") (pin "19") (pinfunction "19_19") (pintype "bidirectional"))
      (node (ref "H2") (pin "22") (pinfunction "22_22") (pintype "bidirectional"))
      (node (ref "H2") (pin "26") (pinfunction "26_26") (pintype "bidirectional"))
      (node (ref "H2") (pin "4") (pinfunction "4_4") (pintype "bidirectional"))
      (node (ref "J4") (pin "1") (pinfunction "C1_1") (pintype "bidirectional"))
      (node (ref "J4") (pin "10") (pinfunction "C10_10") (pintype "bidirectional"))
      (node (ref "J4") (pin "2") (pinfunction "C2_2") (pintype "bidirectional"))
      (node (ref "J4") (pin "27") (pinfunction "C27_27") (pintype "bidirectional"))
      (node (ref "J4") (pin "28") (pinfunction "C28_28") (pintype "bidirectional"))
      (node (ref "J4") (pin "39") (pinfunction "C39_39") (pintype "bidirectional"))
      (node (ref "J4") (pin "40") (pinfunction "C40_40") (pintype "bidirectional"))
      (node (ref "J4") (pin "47") (pinfunction "C47_47") (pintype "bidirectional"))
      (node (ref "J4") (pin "48") (pinfunction "C48_48") (pintype "bidirectional"))
      (node (ref "J4") (pin "7") (pinfunction "C7_7") (pintype "bidirectional"))
      (node (ref "J4") (pin "8") (pinfunction "C8_8") (pintype "bidirectional"))
      (node (ref "J4") (pin "9") (pinfunction "C9_9") (pintype "bidirectional"))
      (node (ref "R11") (pin "2") (pinfunction "2_2") (pintype "passive"))
      (node (ref "R9") (pin "2") (pinfunction "2_2") (pintype "passive"))
      (node (ref "U$4") (pin "2") (pinfunction "GND_2") (pintype "bidirectional"))
      (node (ref "U$5") (pin "-") (pinfunction "-_-") (pintype "passive"))
      (node (ref "U$6") (pin "15") (pinfunction "GND_15") (pintype "bidirectional"))
    )
    (net (code "97") (name "Net-(ADC_TEMP_1-REF_IN)") (class "Default")
      (node (ref "ADC_TEMP_1") (pin "6") (pinfunction "REF_IN_6") (pintype "bidirectional"))
      (node (ref "ADC_TEMP_2") (pin "6") (pinfunction "REF_IN_6") (pintype "bidirectional"))
      (node (ref "C19") (pin "2") (pinfunction "2_2") (pintype "passive"))
      (node (ref "D1") (pin "C") (pinfunction "C_C") (pintype "passive"))
      (node (ref "R17") (pin "1") (pinfunction "1_1") (pintype "passive"))
    )
    (net (code "98") (name "Net-(ADC_TEMP_2-AS)") (class "Default")
      (node (ref "ADC_TEMP_2") (pin "15") (pinfunction "AS_15") (pintype "bidirectional"))
      (node (ref "R16") (pin "2") (pinfunction "2_2") (pintype "passive"))
    )
    (net (code "99") (name "Net-(ADC_TEMP_2-VIN4)") (class "Default")
      (node (ref "ADC_TEMP_2") (pin "13") (pinfunction "VIN4_13") (pintype "bidirectional"))
      (node (ref "C16") (pin "2") (pinfunction "2_2") (pintype "passive"))
      (node (ref "R13") (pin "1") (pinfunction "1_1") (pintype "passive"))
    )
    (net (code "100") (name "Net-(U$5-+)") (class "Default")
      (node (ref "U$5") (pin "+$1") (pinfunction "+_+$1") (pintype "passive"))
      (node (ref "U$5") (pin "+$2") (pinfunction "+1_+$2") (pintype "passive"))
      (node (ref "U$6") (pin "16") (pinfunction "VBAT_16") (pintype "bidirectional"))
    )
    (net (code "101") (name "unconnected-(ADC_TEMP_1-ALERT{slash}BUSY-Pad17)") (class "Default")
      (node (ref "ADC_TEMP_1") (pin "17") (pinfunction "ALERT/BUSY_17") (pintype "bidirectional"))
    )
    (net (code "102") (name "unconnected-(ADC_TEMP_2-ALERT{slash}BUSY-Pad17)") (class "Default")
      (node (ref "ADC_TEMP_2") (pin "17") (pinfunction "ALERT/BUSY_17") (pintype "bidirectional"))
    )
    (net (code "103") (name "unconnected-(ADC_TEMP_2-VIN1-Pad7)") (class "Default")
      (node (ref "ADC_TEMP_2") (pin "7") (pinfunction "VIN1_7") (pintype "bidirectional"))
    )
    (net (code "104") (name "unconnected-(ADC_TEMP_2-VIN2-Pad14)") (class "Default")
      (node (ref "ADC_TEMP_2") (pin "14") (pinfunction "VIN2_14") (pintype "bidirectional"))
    )
    (net (code "105") (name "unconnected-(ADC_TEMP_2-VIN5-Pad9)") (class "Default")
      (node (ref "ADC_TEMP_2") (pin "9") (pinfunction "VIN5_9") (pintype "bidirectional"))
    )
    (net (code "106") (name "unconnected-(ADC_TEMP_2-VIN6-Pad12)") (class "Default")
      (node (ref "ADC_TEMP_2") (pin "12") (pinfunction "VIN6_12") (pintype "bidirectional"))
    )
    (net (code "107") (name "unconnected-(H1-Pad2)") (class "Default")
      (node (ref "H1") (pin "2") (pinfunction "2_2") (pintype "bidirectional"))
    )
    (net (code "108") (name "unconnected-(J2-PadX1)") (class "Default")
      (node (ref "J2") (pin "X1") (pinfunction "X1_X1") (pintype "bidirectional"))
    )
    (net (code "109") (name "unconnected-(J2-PadX2)") (class "Default")
      (node (ref "J2") (pin "X2") (pinfunction "X2_X2") (pintype "bidirectional"))
    )
    (net (code "110") (name "unconnected-(U$6-32KHZ-Pad3)") (class "Default")
      (node (ref "U$6") (pin "3") (pinfunction "32KHZ_3") (pintype "bidirectional"))
    )
    (net (code "111") (name "unconnected-(U$6-N.C.1-Pad1)") (class "Default")
      (node (ref "U$6") (pin "1") (pinfunction "N.C.1_1") (pintype "bidirectional"))
    )
    (net (code "112") (name "unconnected-(U$6-N.C.2-Pad2)") (class "Default")
      (node (ref "U$6") (pin "2") (pinfunction "N.C.2_2") (pintype "bidirectional"))
    )
    (net (code "113") (name "unconnected-(U$6-N.C.3-Pad7)") (class "Default")
      (node (ref "U$6") (pin "7") (pinfunction "N.C.3_7") (pintype "bidirectional"))
    )
    (net (code "114") (name "unconnected-(U$6-N.C.4-Pad8)") (class "Default")
      (node (ref "U$6") (pin "8") (pinfunction "N.C.4_8") (pintype "bidirectional"))
    )
    (net (code "115") (name "unconnected-(U$6-N.C.5-Pad9)") (class "Default")
      (node (ref "U$6") (pin "9") (pinfunction "N.C.5_9") (pintype "bidirectional"))
    )
    (net (code "116") (name "unconnected-(U$6-N.C.6-Pad10)") (class "Default")
      (node (ref "U$6") (pin "10") (pinfunction "N.C.6_10") (pintype "bidirectional"))
    )
    (net (code "117") (name "unconnected-(U$6-N.C.7-Pad11)") (class "Default")
      (node (ref "U$6") (pin "11") (pinfunction "N.C.7_11") (pintype "bidirectional"))
    )
    (net (code "118") (name "unconnected-(U$6-N.C.8-Pad12)") (class "Default")
      (node (ref "U$6") (pin "12") (pinfunction "N.C.8_12") (pintype "bidirectional"))
    )
    (net (code "119") (name "unconnected-(U$6-N.C.9-Pad13)") (class "Default")
      (node (ref "U$6") (pin "13") (pinfunction "N.C.9_13") (pintype "bidirectional"))
    )
    (net (code "120") (name "unconnected-(U$6-N.C.10-Pad14)") (class "Default")
      (node (ref "U$6") (pin "14") (pinfunction "N.C.10_14") (pintype "bidirectional"))
    )
    (net (code "121") (name "unconnected-(U$6-N.C.11-Pad19)") (class "Default")
      (node (ref "U$6") (pin "19") (pinfunction "N.C.11_19") (pintype "bidirectional"))
    )
    (net (code "122") (name "unconnected-(U$6-SCL2-Pad20)") (class "Default")
      (node (ref "U$6") (pin "20") (pinfunction "SCL2_20") (pintype "bidirectional"))
    )
  )
)
